# motor_shield_v1_0.net
KiCad netlist of a schematic drawn in EAGLE
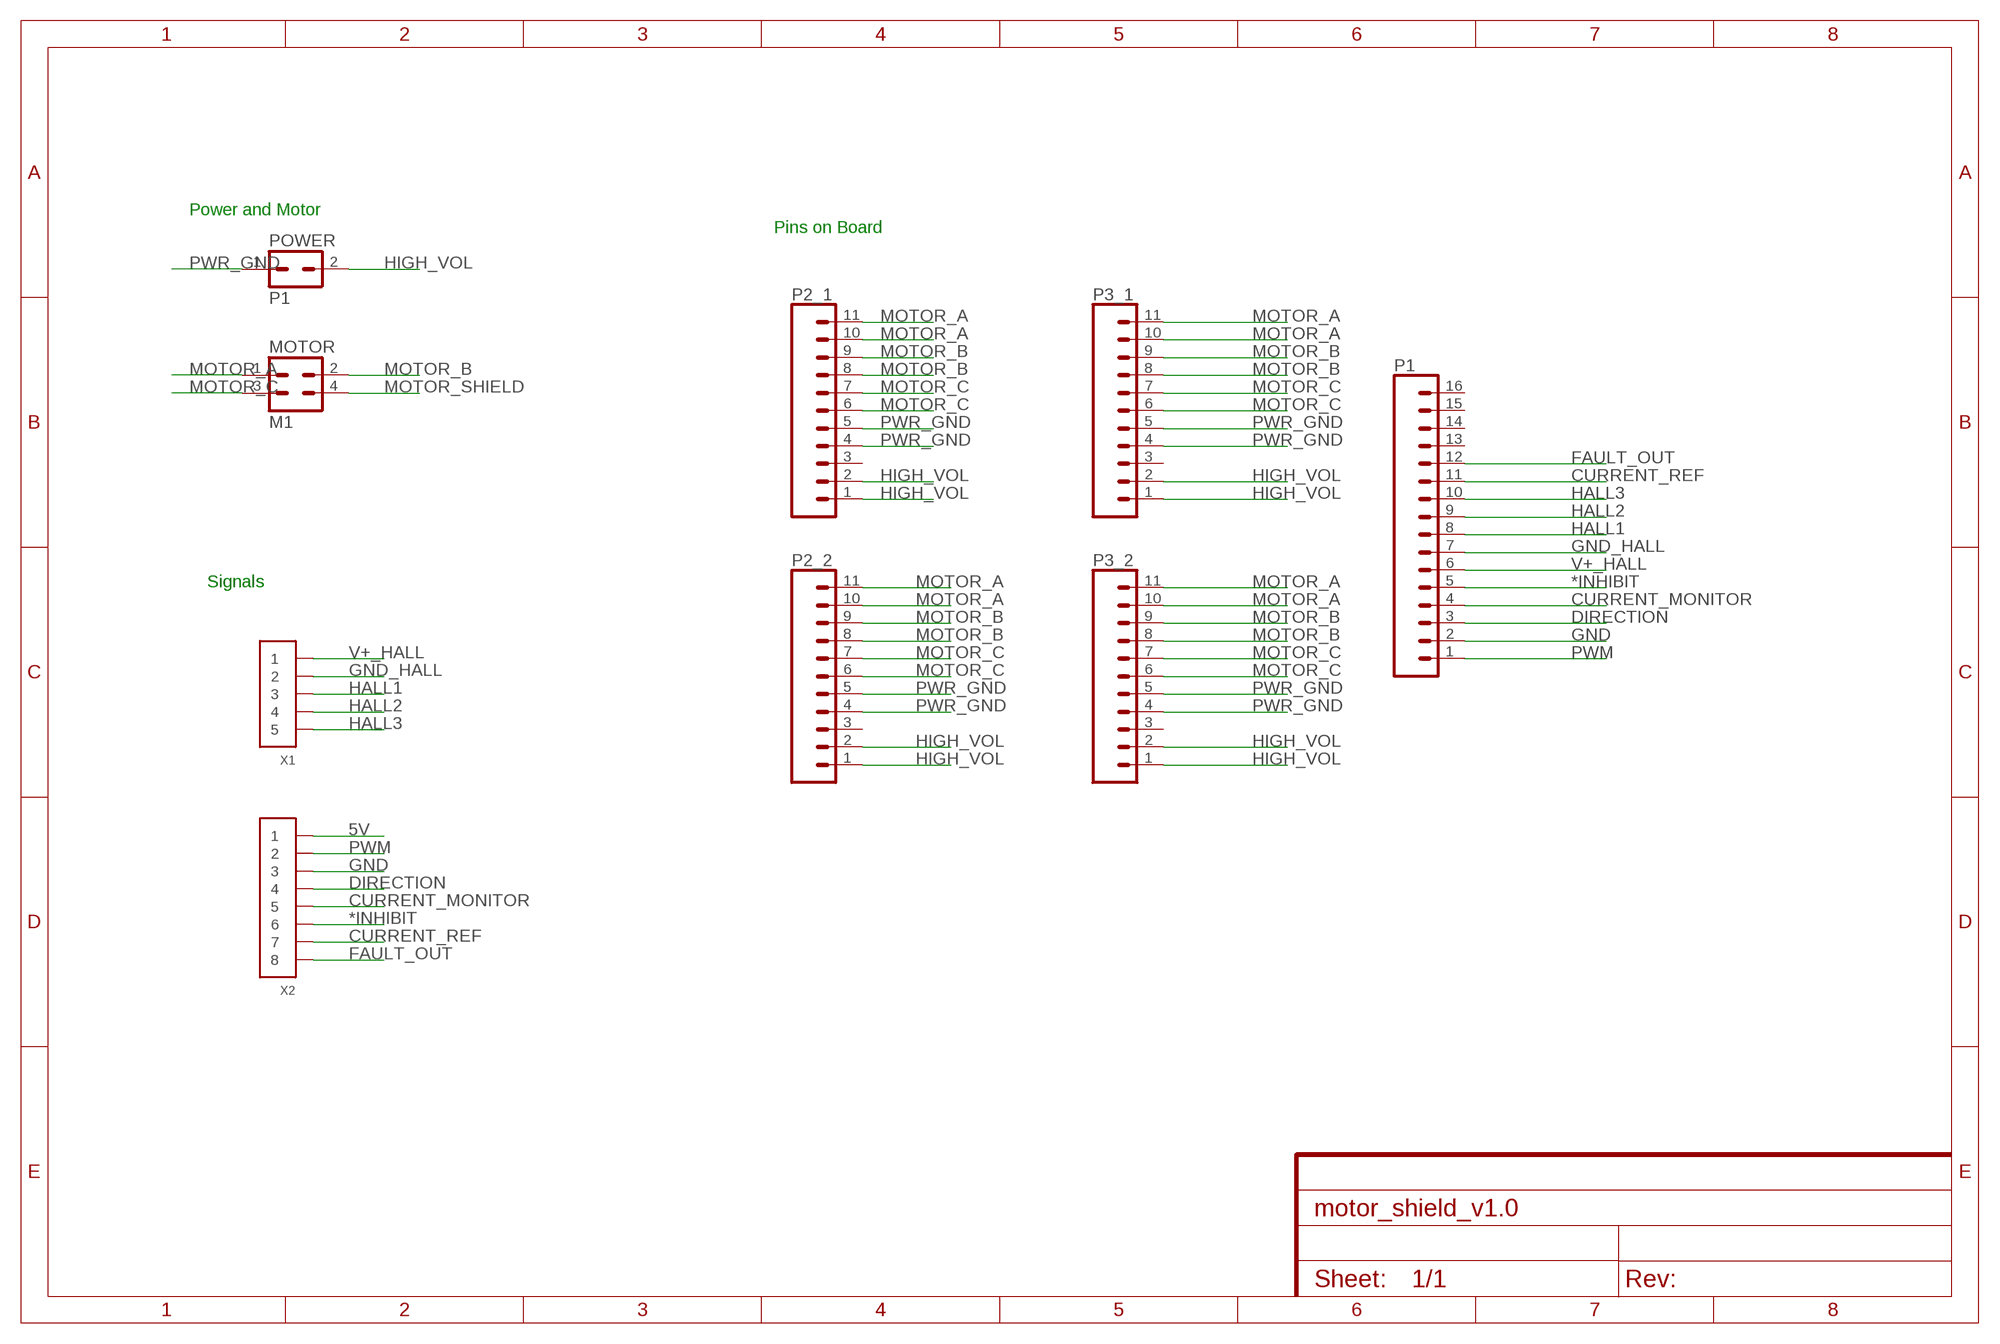
[diagram p0: schematic, sheet 1]

(export (version "E")
  (design (tool "Eeschema 10.0.6"))
  (components
    (comp (ref "MOTOR")
      (value "M1")
      (footprint "eagle-import:39-30-_04_")
      (libsource (lib "eagle-import") (part "39-30-?04?"))
    )
    (comp (ref "P1")
      (value "CONN_16LOCK")
      (footprint "eagle-import:1X16_LOCK")
      (libsource (lib "eagle-import") (part "CONN_16LOCK"))
    )
    (comp (ref "P2_1")
      (value "CONN_11")
      (footprint "eagle-import:1X11")
      (libsource (lib "eagle-import") (part "CONN_11"))
    )
    (comp (ref "P2_2")
      (value "CONN_11")
      (footprint "eagle-import:1X11")
      (libsource (lib "eagle-import") (part "CONN_11"))
    )
    (comp (ref "P3_1")
      (value "CONN_11")
      (footprint "eagle-import:1X11")
      (libsource (lib "eagle-import") (part "CONN_11"))
    )
    (comp (ref "P3_2")
      (value "CONN_11")
      (footprint "eagle-import:1X11")
      (libsource (lib "eagle-import") (part "CONN_11"))
    )
    (comp (ref "POWER")
      (value "P1")
      (footprint "eagle-import:39-30-_02_")
      (libsource (lib "eagle-import") (part "39-30-?02?"))
    )
    (comp (ref "X1")
      (value "CONN_5-1-53261")
      (footprint "eagle-import:PB-53261-05")
      (libsource (lib "eagle-import") (part "CONN_5-1-53261"))
    )
    (comp (ref "X2")
      (value "CONN_8-1-53261")
      (footprint "eagle-import:PB-53261-08")
      (libsource (lib "eagle-import") (part "CONN_8-1-53261"))
    )
  )
  (nets
    (net (code "1") (name "/*INHIBIT") (class "Default")
      (node (ref "P1") (pin "5") (pinfunction "5_5") (pintype "passive"))
      (node (ref "X2") (pin "6") (pinfunction "6_6") (pintype "bidirectional"))
    )
    (net (code "2") (name "/5V") (class "Default")
      (node (ref "X2") (pin "1") (pinfunction "1_1") (pintype "bidirectional"))
    )
    (net (code "3") (name "/CURRENT_MONITOR") (class "Default")
      (node (ref "P1") (pin "4") (pinfunction "4_4") (pintype "passive"))
      (node (ref "X2") (pin "5") (pinfunction "5_5") (pintype "bidirectional"))
    )
    (net (code "4") (name "/CURRENT_REF") (class "Default")
      (node (ref "P1") (pin "11") (pinfunction "11_11") (pintype "passive"))
      (node (ref "X2") (pin "7") (pinfunction "7_7") (pintype "bidirectional"))
    )
    (net (code "5") (name "/DIRECTION") (class "Default")
      (node (ref "P1") (pin "3") (pinfunction "3_3") (pintype "passive"))
      (node (ref "X2") (pin "4") (pinfunction "4_4") (pintype "bidirectional"))
    )
    (net (code "6") (name "/FAULT_OUT") (class "Default")
      (node (ref "P1") (pin "12") (pinfunction "12_12") (pintype "passive"))
      (node (ref "X2") (pin "8") (pinfunction "8_8") (pintype "bidirectional"))
    )
    (net (code "7") (name "/GND") (class "Default")
      (node (ref "P1") (pin "2") (pinfunction "2_2") (pintype "passive"))
      (node (ref "X2") (pin "3") (pinfunction "3_3") (pintype "bidirectional"))
    )
    (net (code "8") (name "/GND_HALL") (class "Default")
      (node (ref "P1") (pin "7") (pinfunction "7_7") (pintype "passive"))
      (node (ref "X1") (pin "2") (pinfunction "2_2") (pintype "bidirectional"))
    )
    (net (code "9") (name "/HALL1") (class "Default")
      (node (ref "P1") (pin "8") (pinfunction "8_8") (pintype "passive"))
      (node (ref "X1") (pin "3") (pinfunction "3_3") (pintype "bidirectional"))
    )
    (net (code "10") (name "/HALL2") (class "Default")
      (node (ref "P1") (pin "9") (pinfunction "9_9") (pintype "passive"))
      (node (ref "X1") (pin "4") (pinfunction "4_4") (pintype "bidirectional"))
    )
    (net (code "11") (name "/HALL3") (class "Default")
      (node (ref "P1") (pin "10") (pinfunction "10_10") (pintype "passive"))
      (node (ref "X1") (pin "5") (pinfunction "5_5") (pintype "bidirectional"))
    )
    (net (code "12") (name "/HIGH_VOL") (class "Default")
      (node (ref "P2_1") (pin "1") (pinfunction "1_1") (pintype "passive"))
      (node (ref "P2_1") (pin "2") (pinfunction "2_2") (pintype "passive"))
      (node (ref "P2_2") (pin "1") (pinfunction "1_1") (pintype "passive"))
      (node (ref "P2_2") (pin "2") (pinfunction "2_2") (pintype "passive"))
      (node (ref "P3_1") (pin "1") (pinfunction "1_1") (pintype "passive"))
      (node (ref "P3_1") (pin "2") (pinfunction "2_2") (pintype "passive"))
      (node (ref "P3_2") (pin "1") (pinfunction "1_1") (pintype "passive"))
      (node (ref "P3_2") (pin "2") (pinfunction "2_2") (pintype "passive"))
      (node (ref "POWER") (pin "2") (pinfunction "2_2") (pintype "passive"))
    )
    (net (code "13") (name "/MOTOR_A") (class "Default")
      (node (ref "MOTOR") (pin "1") (pinfunction "1_1") (pintype "passive"))
      (node (ref "P2_1") (pin "10") (pinfunction "10_10") (pintype "passive"))
      (node (ref "P2_1") (pin "11") (pinfunction "11_11") (pintype "passive"))
      (node (ref "P2_2") (pin "10") (pinfunction "10_10") (pintype "passive"))
      (node (ref "P2_2") (pin "11") (pinfunction "11_11") (pintype "passive"))
      (node (ref "P3_1") (pin "10") (pinfunction "10_10") (pintype "passive"))
      (node (ref "P3_1") (pin "11") (pinfunction "11_11") (pintype "passive"))
      (node (ref "P3_2") (pin "10") (pinfunction "10_10") (pintype "passive"))
      (node (ref "P3_2") (pin "11") (pinfunction "11_11") (pintype "passive"))
    )
    (net (code "14") (name "/MOTOR_B") (class "Default")
      (node (ref "MOTOR") (pin "2") (pinfunction "2_2") (pintype "passive"))
      (node (ref "P2_1") (pin "8") (pinfunction "8_8") (pintype "passive"))
      (node (ref "P2_1") (pin "9") (pinfunction "9_9") (pintype "passive"))
      (node (ref "P2_2") (pin "8") (pinfunction "8_8") (pintype "passive"))
      (node (ref "P2_2") (pin "9") (pinfunction "9_9") (pintype "passive"))
      (node (ref "P3_1") (pin "8") (pinfunction "8_8") (pintype "passive"))
      (node (ref "P3_1") (pin "9") (pinfunction "9_9") (pintype "passive"))
      (node (ref "P3_2") (pin "8") (pinfunction "8_8") (pintype "passive"))
      (node (ref "P3_2") (pin "9") (pinfunction "9_9") (pintype "passive"))
    )
    (net (code "15") (name "/MOTOR_C") (class "Default")
      (node (ref "MOTOR") (pin "3") (pinfunction "3_3") (pintype "passive"))
      (node (ref "P2_1") (pin "6") (pinfunction "6_6") (pintype "passive"))
      (node (ref "P2_1") (pin "7") (pinfunction "7_7") (pintype "passive"))
      (node (ref "P2_2") (pin "6") (pinfunction "6_6") (pintype "passive"))
      (node (ref "P2_2") (pin "7") (pinfunction "7_7") (pintype "passive"))
      (node (ref "P3_1") (pin "6") (pinfunction "6_6") (pintype "passive"))
      (node (ref "P3_1") (pin "7") (pinfunction "7_7") (pintype "passive"))
      (node (ref "P3_2") (pin "6") (pinfunction "6_6") (pintype "passive"))
      (node (ref "P3_2") (pin "7") (pinfunction "7_7") (pintype "passive"))
    )
    (net (code "16") (name "/MOTOR_SHIELD") (class "Default")
      (node (ref "MOTOR") (pin "4") (pinfunction "4_4") (pintype "passive"))
    )
    (net (code "17") (name "/PWM") (class "Default")
      (node (ref "P1") (pin "1") (pinfunction "1_1") (pintype "passive"))
      (node (ref "X2") (pin "2") (pinfunction "2_2") (pintype "bidirectional"))
    )
    (net (code "18") (name "/PWR_GND") (class "Default")
      (node (ref "P2_1") (pin "4") (pinfunction "4_4") (pintype "passive"))
      (node (ref "P2_1") (pin "5") (pinfunction "5_5") (pintype "passive"))
      (node (ref "P2_2") (pin "4") (pinfunction "4_4") (pintype "passive"))
      (node (ref "P2_2") (pin "5") (pinfunction "5_5") (pintype "passive"))
      (node (ref "P3_1") (pin "4") (pinfunction "4_4") (pintype "passive"))
      (node (ref "P3_1") (pin "5") (pinfunction "5_5") (pintype "passive"))
      (node (ref "P3_2") (pin "4") (pinfunction "4_4") (pintype "passive"))
      (node (ref "P3_2") (pin "5") (pinfunction "5_5") (pintype "passive"))
      (node (ref "POWER") (pin "1") (pinfunction "1_1") (pintype "passive"))
    )
    (net (code "19") (name "/V+_HALL") (class "Default")
      (node (ref "P1") (pin "6") (pinfunction "6_6") (pintype "passive"))
      (node (ref "X1") (pin "1") (pinfunction "1_1") (pintype "bidirectional"))
    )
    (net (code "20") (name "unconnected-(P1-Pad13)") (class "Default")
      (node (ref "P1") (pin "13") (pinfunction "13_13") (pintype "passive"))
    )
    (net (code "21") (name "unconnected-(P1-Pad14)") (class "Default")
      (node (ref "P1") (pin "14") (pinfunction "14_14") (pintype "passive"))
    )
    (net (code "22") (name "unconnected-(P1-Pad15)") (class "Default")
      (node (ref "P1") (pin "15") (pinfunction "15_15") (pintype "passive"))
    )
    (net (code "23") (name "unconnected-(P1-Pad16)") (class "Default")
      (node (ref "P1") (pin "16") (pinfunction "16_16") (pintype "passive"))
    )
    (net (code "24") (name "unconnected-(P2_1-Pad3)") (class "Default")
      (node (ref "P2_1") (pin "3") (pinfunction "3_3") (pintype "passive"))
    )
    (net (code "25") (name "unconnected-(P2_2-Pad3)") (class "Default")
      (node (ref "P2_2") (pin "3") (pinfunction "3_3") (pintype "passive"))
    )
    (net (code "26") (name "unconnected-(P3_1-Pad3)") (class "Default")
      (node (ref "P3_1") (pin "3") (pinfunction "3_3") (pintype "passive"))
    )
    (net (code "27") (name "unconnected-(P3_2-Pad3)") (class "Default")
      (node (ref "P3_2") (pin "3") (pinfunction "3_3") (pintype "passive"))
    )
  )
)
